# Sheet3.net
KiCad netlist of a schematic drawn in Altium Designer
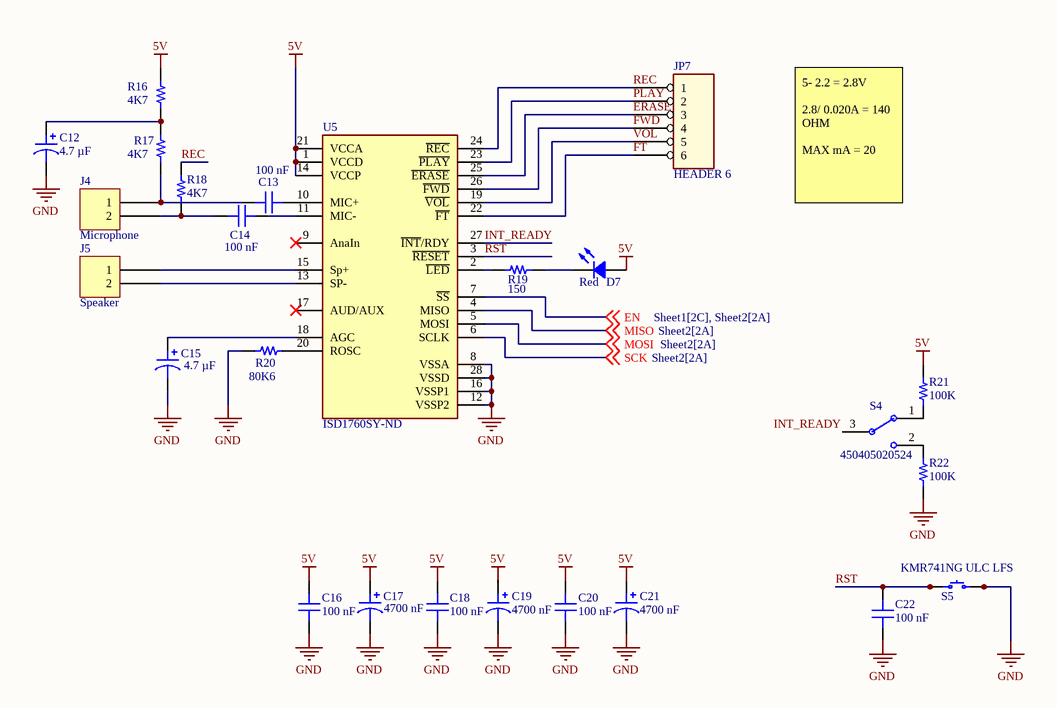
[diagram p0: Sheet3.SchDoc]

(export (version "E")
  (design (tool "Eeschema 10.0.6"))
  (components
    (comp (ref "C12")
      (value "4.7 µF")
      (footprint "CAP ALUM 4.3MM2")
      (description "CAP ALUM 4.7UF 20% 35V SMD")
      (fields
        (field (name "PART NUMBER") "EMVE350ADA4R7MD55G")
        (field (name "MANUFACTURER") "United Chemi-Con")
      )
      (libsource (lib "Celestial Altium Library - altium_library") (part "Polarised Capacitor"))
    )
    (comp (ref "C13")
      (value "100 nF")
      (footprint "CAP 0603")
      (description "CAP CER 0.1UF 16V X7R 0603")
      (fields (field (name "PART NUMBER") "CS0603KRX7R7BB104") (field (name "MANUFACTURER") "Yageo"))
      (libsource (lib "Celestial Altium Library - altium_library") (part "Capacitor"))
    )
    (comp (ref "C14")
      (value "100 nF")
      (footprint "CAP 0603")
      (description "CAP CER 0.1UF 16V X7R 0603")
      (fields (field (name "PART NUMBER") "CS0603KRX7R7BB104") (field (name "MANUFACTURER") "Yageo"))
      (libsource (lib "Celestial Altium Library - altium_library") (part "Capacitor"))
    )
    (comp (ref "C15")
      (value "4.7 µF")
      (footprint "CAP ALUM 4.3MM2")
      (description "CAP ALUM 4.7UF 20% 35V SMD")
      (fields
        (field (name "PART NUMBER") "EMVE350ADA4R7MD55G")
        (field (name "MANUFACTURER") "United Chemi-Con")
      )
      (libsource (lib "Celestial Altium Library - altium_library") (part "Polarised Capacitor"))
    )
    (comp (ref "C16")
      (value "100 nF")
      (footprint "CAP 0603")
      (description "CAP CER 0.1UF 16V X7R 0603")
      (fields (field (name "PART NUMBER") "CS0603KRX7R7BB104") (field (name "MANUFACTURER") "Yageo"))
      (libsource (lib "Celestial Altium Library - altium_library") (part "Capacitor"))
    )
    (comp (ref "C17")
      (value "4700 nF")
      (footprint "CAP ALSMD ELEC 4.3MM H5.4MM")
      (description "CAP ALUM 4.7UF 20% 35V SMD")
      (fields
        (field (name "PART NUMBER") "EMVE350ADA4R7MD55G")
        (field (name "MANUFACTURER") "United Chemi-Con")
      )
      (libsource (lib "Celestial Altium Library - altium_library") (part "Polarised Capacitor"))
    )
    (comp (ref "C18")
      (value "100 nF")
      (footprint "CAP 0603")
      (description "CAP CER 0.1UF 16V X7R 0603")
      (fields (field (name "PART NUMBER") "CS0603KRX7R7BB104") (field (name "MANUFACTURER") "Yageo"))
      (libsource (lib "Celestial Altium Library - altium_library") (part "Capacitor"))
    )
    (comp (ref "C19")
      (value "4700 nF")
      (footprint "CAP ALSMD ELEC 4.3MM H5.4MM")
      (description "CAP ALUM 4.7UF 20% 35V SMD")
      (fields
        (field (name "PART NUMBER") "EMVE350ADA4R7MD55G")
        (field (name "MANUFACTURER") "United Chemi-Con")
      )
      (libsource (lib "Celestial Altium Library - altium_library") (part "Polarised Capacitor"))
    )
    (comp (ref "C20")
      (value "100 nF")
      (footprint "CAP 0603")
      (description "CAP CER 0.1UF 16V X7R 0603")
      (fields (field (name "PART NUMBER") "CS0603KRX7R7BB104") (field (name "MANUFACTURER") "Yageo"))
      (libsource (lib "Celestial Altium Library - altium_library") (part "Capacitor"))
    )
    (comp (ref "C21")
      (value "4700 nF")
      (footprint "CAP ALUM 4.3MM2")
      (description "CAP ALUM 4.7UF 20% 35V SMD")
      (fields
        (field (name "PART NUMBER") "EMVE350ADA4R7MD55G")
        (field (name "MANUFACTURER") "United Chemi-Con")
      )
      (libsource (lib "Celestial Altium Library - altium_library") (part "Polarised Capacitor"))
    )
    (comp (ref "C22")
      (value "100 nF")
      (footprint "CAP 0603")
      (description "CAP CER 0.1UF 16V X7R 0603")
      (fields (field (name "PART NUMBER") "CS0603KRX7R7BB104") (field (name "MANUFACTURER") "Yageo"))
      (libsource (lib "Celestial Altium Library - altium_library") (part "Capacitor"))
    )
    (comp (ref "D7")
      (value "Red")
      (footprint "Blue LED 0603")
      (description "0603 RED")
      (fields
        (field (name "PART NUMBER") "BL-HUB36A-AV-TRB")
        (field (name "MANUFACTURER") "American Bright Optoelectronics Corporation")
      )
      (libsource (lib "Celestial Altium Library - altium_library") (part "LED"))
    )
    (comp (ref "J4")
      (value "Microphone")
      (footprint "CONN FEM HEADER 2PIN")
      (description "TERM BLK 2P SIDE ENT 2.54MM PCB")
      (fields
        (field (name "PART NUMBER") "282834-2")
        (field (name "MANUFACTURER") "TE Connectivity AMP Connectors")
      )
      (libsource (lib "Celestial Altium Library - altium_library") (part "2 Pin"))
    )
    (comp (ref "J5")
      (value "Speaker")
      (footprint "CONN FEM HEADER 2PIN")
      (description "TERM BLK 2P SIDE ENT 2.54MM PCB")
      (fields
        (field (name "PART NUMBER") "282834-2")
        (field (name "MANUFACTURER") "TE Connectivity AMP Connectors")
      )
      (libsource (lib "Celestial Altium Library - altium_library") (part "2 Pin"))
    )
    (comp (ref "JP7")
      (value "HEADER 6")
      (footprint "J\\6P")
      (libsource (lib "PCBDEV_Library") (part "HEADER 6"))
    )
    (comp (ref "R16")
      (value "4K7")
      (footprint "RES 0603")
      (description "RES 4.7K OHM 1% 1/10W 0603")
      (fields
        (field (name "PART NUMBER") "RMCF0603FT4K70")
        (field (name "MANUFACTURER") "Stackpole Electronics Inc")
      )
      (libsource (lib "Celestial Altium Library - altium_library") (part "Resistor"))
    )
    (comp (ref "R17")
      (value "4K7")
      (footprint "RES 0603")
      (description "RES 4.7K OHM 1% 1/10W 0603")
      (fields
        (field (name "PART NUMBER") "RMCF0603FT4K70")
        (field (name "MANUFACTURER") "Stackpole Electronics Inc")
      )
      (libsource (lib "Celestial Altium Library - altium_library") (part "Resistor"))
    )
    (comp (ref "R18")
      (value "4K7")
      (footprint "RES 0603")
      (description "RES 4.7K OHM 1% 1/10W 0603")
      (fields
        (field (name "PART NUMBER") "RMCF0603FT4K70")
        (field (name "MANUFACTURER") "Stackpole Electronics Inc")
      )
      (libsource (lib "Celestial Altium Library - altium_library") (part "Resistor"))
    )
    (comp (ref "R19")
      (value "150")
      (footprint "RES 0603")
      (description "RES SMD 150 OHM 0.1% 1/8W 0603")
      (fields
        (field (name "PART NUMBER") "MCT0603MD1500BP100")
        (field (name "MANUFACTURER") "Vishay Beyschlag")
      )
      (libsource (lib "Celestial Altium Library - altium_library") (part "Resistor"))
    )
    (comp (ref "R20")
      (value "80K6")
      (footprint "RES 0603")
      (description "RES SMD 80.6K OHM 1% 1/4W 0603")
      (fields (field (name "PART NUMBER") "RCS060380K6FKEA") (field (name "MANUFACTURER") "Vishay Dale"))
      (libsource (lib "Celestial Altium Library - altium_library") (part "Resistor"))
    )
    (comp (ref "R21")
      (value "100K")
      (footprint "RES 0603")
      (description "RESHIGHPOWERA 0603 100K 1% 1/4W")
      (fields (field (name "PART NUMBER") "CMP0603AFX-1003ELF") (field (name "MANUFACTURER") "Bourns Inc."))
      (libsource (lib "Celestial Altium Library - altium_library") (part "Resistor"))
    )
    (comp (ref "R22")
      (value "100K")
      (footprint "RES 0603")
      (description "RESHIGHPOWERA 0603 100K 1% 1/4W")
      (fields (field (name "PART NUMBER") "CMP0603AFX-1003ELF") (field (name "MANUFACTURER") "Bourns Inc."))
      (libsource (lib "Celestial Altium Library - altium_library") (part "Resistor"))
    )
    (comp (ref "S4")
      (value "450405020524")
      (footprint "SL 3Pos Switch")
      (description "SMT 8.7 X 3.0 MM MINI SLIDE SWIT")
      (fields (field (name "MANUFACTURER") "Würth Elektronik") (field (name "PUBLISHER") "Wurth Elektronik"))
      (libsource (lib "Celestial Altium Library - altium_library") (part "WURTH WS-SLSU 450405020524"))
    )
    (comp (ref "S5")
      (value "KMR741NG ULC LFS")
      (footprint "Switch Lin SMD")
      (description "SWITCH TACTILE SPST-NO 50MA 32V")
      (fields (field (name "MANUFACTURER") "C&K"))
      (libsource (lib "Celestial Altium Library - altium_library") (part "SPST-NO 4 PIN"))
    )
    (comp (ref "U5")
      (value "ISD1760SY")
      (footprint "ISD1760SY")
      (description "Voice Record/Playback IC Multiple Message 40 ~ 120 Sec Pushbutton, SPI 28-SOIC")
      (fields (field (name "SUPPLIER PART NUMBER 1") "ISD1760SY-ND"))
      (libsource (lib "ISD1760SY") (part "ISD1760SY"))
    )
  )
  (nets
    (net (code "1") (name "/ERASE") (class "Default")
      (node (ref "JP7") (pin "3") (pinfunction "3_3") (pintype "passive"))
      (node (ref "U5") (pin "25") (pinfunction "~{ERASE}_25") (pintype "passive"))
    )
    (net (code "2") (name "/FT") (class "Default")
      (node (ref "JP7") (pin "6") (pinfunction "6_6") (pintype "passive"))
      (node (ref "U5") (pin "22") (pinfunction "~{FT}_22") (pintype "passive"))
    )
    (net (code "3") (name "/FWD") (class "Default")
      (node (ref "JP7") (pin "4") (pinfunction "4_4") (pintype "passive"))
      (node (ref "U5") (pin "26") (pinfunction "~{FWD}_26") (pintype "passive"))
    )
    (net (code "4") (name "/INT_READY") (class "Default")
      (node (ref "S4") (pin "3") (pinfunction "COM_3") (pintype "passive"))
      (node (ref "U5") (pin "27") (pinfunction "~{INT}/RDY_27") (pintype "passive"))
    )
    (net (code "5") (name "/PLAY") (class "Default")
      (node (ref "JP7") (pin "2") (pinfunction "2_2") (pintype "passive"))
      (node (ref "U5") (pin "23") (pinfunction "~{PLAY}_23") (pintype "passive"))
    )
    (net (code "6") (name "/REC") (class "Default")
      (node (ref "JP7") (pin "1") (pinfunction "1_1") (pintype "passive"))
      (node (ref "R18") (pin "2") (pinfunction "2_2") (pintype "passive"))
      (node (ref "U5") (pin "24") (pinfunction "~{REC}_24") (pintype "passive"))
    )
    (net (code "7") (name "/RST") (class "Default")
      (node (ref "C22") (pin "2") (pinfunction "2_2") (pintype "passive"))
      (node (ref "S5") (pin "1") (pinfunction "1_1") (pintype "passive"))
      (node (ref "S5") (pin "2") (pinfunction "2_2") (pintype "passive"))
      (node (ref "U5") (pin "3") (pinfunction "~{RESET}_3") (pintype "passive"))
    )
    (net (code "8") (name "/VOL") (class "Default")
      (node (ref "JP7") (pin "5") (pinfunction "5_5") (pintype "passive"))
      (node (ref "U5") (pin "19") (pinfunction "~{VOL}_19") (pintype "passive"))
    )
    (net (code "9") (name "5V") (class "Default")
      (node (ref "C16") (pin "2") (pinfunction "2_2") (pintype "passive"))
      (node (ref "C17") (pin "1") (pinfunction "1_1") (pintype "passive"))
      (node (ref "C18") (pin "2") (pinfunction "2_2") (pintype "passive"))
      (node (ref "C19") (pin "1") (pinfunction "1_1") (pintype "passive"))
      (node (ref "C20") (pin "2") (pinfunction "2_2") (pintype "passive"))
      (node (ref "C21") (pin "1") (pinfunction "1_1") (pintype "passive"))
      (node (ref "D7") (pin "1") (pinfunction "1_1") (pintype "passive"))
      (node (ref "R16") (pin "2") (pinfunction "2_2") (pintype "passive"))
      (node (ref "R21") (pin "2") (pinfunction "2_2") (pintype "passive"))
      (node (ref "U5") (pin "1") (pinfunction "VCCD_1") (pintype "passive"))
      (node (ref "U5") (pin "14") (pinfunction "VCCP_14") (pintype "passive"))
      (node (ref "U5") (pin "21") (pinfunction "VCCA_21") (pintype "passive"))
    )
    (net (code "10") (name "EN") (class "Default")
      (node (ref "U5") (pin "7") (pinfunction "~{SS}_7") (pintype "passive"))
    )
    (net (code "11") (name "GND") (class "Default")
      (node (ref "C12") (pin "2") (pinfunction "2_2") (pintype "passive"))
      (node (ref "C15") (pin "2") (pinfunction "2_2") (pintype "passive"))
      (node (ref "C16") (pin "1") (pinfunction "1_1") (pintype "passive"))
      (node (ref "C17") (pin "2") (pinfunction "2_2") (pintype "passive"))
      (node (ref "C18") (pin "1") (pinfunction "1_1") (pintype "passive"))
      (node (ref "C19") (pin "2") (pinfunction "2_2") (pintype "passive"))
      (node (ref "C20") (pin "1") (pinfunction "1_1") (pintype "passive"))
      (node (ref "C21") (pin "2") (pinfunction "2_2") (pintype "passive"))
      (node (ref "C22") (pin "1") (pinfunction "1_1") (pintype "passive"))
      (node (ref "R20") (pin "1") (pinfunction "1_1") (pintype "passive"))
      (node (ref "R22") (pin "1") (pinfunction "1_1") (pintype "passive"))
      (node (ref "S5") (pin "3") (pinfunction "3_3") (pintype "passive"))
      (node (ref "S5") (pin "4") (pinfunction "4_4") (pintype "passive"))
      (node (ref "U5") (pin "12") (pinfunction "VSSP2_12") (pintype "passive"))
      (node (ref "U5") (pin "16") (pinfunction "VSSP1_16") (pintype "passive"))
      (node (ref "U5") (pin "28") (pinfunction "VSSD_28") (pintype "passive"))
      (node (ref "U5") (pin "8") (pinfunction "VSSA_8") (pintype "passive"))
    )
    (net (code "12") (name "MISO") (class "Default")
      (node (ref "U5") (pin "4") (pinfunction "MISO_4") (pintype "passive"))
    )
    (net (code "13") (name "MOSI") (class "Default")
      (node (ref "U5") (pin "5") (pinfunction "MOSI_5") (pintype "passive"))
    )
    (net (code "14") (name "Net-(C12-Pad1)") (class "Default")
      (node (ref "C12") (pin "1") (pinfunction "1_1") (pintype "passive"))
      (node (ref "R16") (pin "1") (pinfunction "1_1") (pintype "passive"))
      (node (ref "R17") (pin "2") (pinfunction "2_2") (pintype "passive"))
    )
    (net (code "15") (name "Net-(C13-Pad2)") (class "Default")
      (node (ref "C13") (pin "2") (pinfunction "2_2") (pintype "passive"))
      (node (ref "J4") (pin "1") (pinfunction "1_1") (pintype "passive"))
      (node (ref "R17") (pin "1") (pinfunction "1_1") (pintype "passive"))
    )
    (net (code "16") (name "Net-(C14-Pad2)") (class "Default")
      (node (ref "C14") (pin "2") (pinfunction "2_2") (pintype "passive"))
      (node (ref "J4") (pin "2") (pinfunction "2_2") (pintype "passive"))
      (node (ref "R18") (pin "1") (pinfunction "1_1") (pintype "passive"))
    )
    (net (code "17") (name "Net-(D7-Pad2)") (class "Default")
      (node (ref "D7") (pin "2") (pinfunction "2_2") (pintype "passive"))
      (node (ref "R19") (pin "2") (pinfunction "2_2") (pintype "passive"))
    )
    (net (code "18") (name "Net-(R21-Pad1)") (class "Default")
      (node (ref "R21") (pin "1") (pinfunction "1_1") (pintype "passive"))
      (node (ref "S4") (pin "1") (pinfunction "1_1") (pintype "passive"))
    )
    (net (code "19") (name "Net-(R22-Pad2)") (class "Default")
      (node (ref "R22") (pin "2") (pinfunction "2_2") (pintype "passive"))
      (node (ref "S4") (pin "2") (pinfunction "2_2") (pintype "passive"))
    )
    (net (code "20") (name "Net-(U5-AGC)") (class "Default")
      (node (ref "C15") (pin "1") (pinfunction "1_1") (pintype "passive"))
      (node (ref "U5") (pin "18") (pinfunction "AGC_18") (pintype "passive"))
    )
    (net (code "21") (name "Net-(U5-MIC+)") (class "Default")
      (node (ref "C13") (pin "1") (pinfunction "1_1") (pintype "passive"))
      (node (ref "U5") (pin "10") (pinfunction "MIC+_10") (pintype "passive"))
    )
    (net (code "22") (name "Net-(U5-MIC-)") (class "Default")
      (node (ref "C14") (pin "1") (pinfunction "1_1") (pintype "passive"))
      (node (ref "U5") (pin "11") (pinfunction "MIC-_11") (pintype "passive"))
    )
    (net (code "23") (name "Net-(U5-ROSC)") (class "Default")
      (node (ref "R20") (pin "2") (pinfunction "2_2") (pintype "passive"))
      (node (ref "U5") (pin "20") (pinfunction "ROSC_20") (pintype "passive"))
    )
    (net (code "24") (name "Net-(U5-SP-)") (class "Default")
      (node (ref "J5") (pin "2") (pinfunction "2_2") (pintype "passive"))
      (node (ref "U5") (pin "13") (pinfunction "SP-_13") (pintype "passive"))
    )
    (net (code "25") (name "Net-(U5-Sp+)") (class "Default")
      (node (ref "J5") (pin "1") (pinfunction "1_1") (pintype "passive"))
      (node (ref "U5") (pin "15") (pinfunction "Sp+_15") (pintype "passive"))
    )
    (net (code "26") (name "Net-(U5-~{LED})") (class "Default")
      (node (ref "R19") (pin "1") (pinfunction "1_1") (pintype "passive"))
      (node (ref "U5") (pin "2") (pinfunction "~{LED}_2") (pintype "passive"))
    )
    (net (code "27") (name "SCK") (class "Default")
      (node (ref "U5") (pin "6") (pinfunction "SCLK_6") (pintype "passive"))
    )
    (net (code "28") (name "unconnected-(U5-AUD{slash}AUX-Pad17)") (class "Default")
      (node (ref "U5") (pin "17") (pinfunction "AUD/AUX_17") (pintype "passive+no_connect"))
    )
    (net (code "29") (name "unconnected-(U5-AnaIn-Pad9)") (class "Default")
      (node (ref "U5") (pin "9") (pinfunction "AnaIn_9") (pintype "passive+no_connect"))
    )
  )
)
